# LoRa.net
KiCad netlist of a schematic drawn in Altium Designer
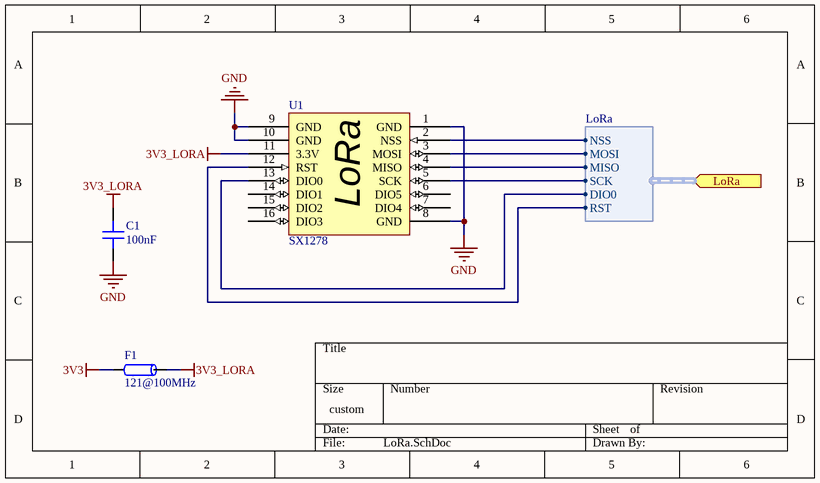
[diagram p0: LoRa.SchDoc]

(export (version "E")
  (design (tool "Eeschema 10.0.6"))
  (components
    (comp (ref "C1")
      (value "100nF")
      (footprint "CAP 0603_1608")
      (description "SMT Capacitor")
      (libsource (lib "Capacitor") (part "Cap 0603"))
    )
    (comp (ref "F1")
      (value "121@100MHz")
      (footprint "Ferrite-0805")
      (description "Ferrite Bead")
      (libsource (lib "Salman_lib") (part "Ferrite Bead"))
    )
    (comp (ref "U1")
      (value "SX1278")
      (footprint "LoRa-Ra-02")
      (libsource (lib "Salman_lib") (part "LoRa Ra-02"))
    )
  )
  (nets
    (net (code "2") (name "/DIO0") (class "Default")
      (node (ref "U1") (pin "13") (pinfunction "DIO0_13") (pintype "bidirectional"))
    )
    (net (code "3") (name "/MISO") (class "Default")
      (node (ref "U1") (pin "4") (pinfunction "MISO_4") (pintype "bidirectional"))
    )
    (net (code "4") (name "/MOSI") (class "Default")
      (node (ref "U1") (pin "3") (pinfunction "MOSI_3") (pintype "bidirectional"))
    )
    (net (code "5") (name "/NSS") (class "Default")
      (node (ref "U1") (pin "2") (pinfunction "NSS_2") (pintype "input"))
    )
    (net (code "6") (name "/RST") (class "Default")
      (node (ref "U1") (pin "12") (pinfunction "RST_12") (pintype "input"))
    )
    (net (code "7") (name "/SCK") (class "Default")
      (node (ref "U1") (pin "5") (pinfunction "SCK_5") (pintype "bidirectional"))
    )
    (net (code "9") (name "3V3") (class "Default")
      (node (ref "F1") (pin "1") (pinfunction "67_1") (pintype "passive"))
    )
    (net (code "10") (name "3V3_LORA") (class "Default")
      (node (ref "C1") (pin "2") (pinfunction "2_2") (pintype "passive"))
      (node (ref "F1") (pin "2") (pinfunction "66_2") (pintype "passive"))
      (node (ref "U1") (pin "11") (pinfunction "3.3V_11") (pintype "power_in"))
    )
    (net (code "11") (name "GND") (class "Default")
      (node (ref "C1") (pin "1") (pinfunction "1_1") (pintype "passive"))
      (node (ref "U1") (pin "1") (pinfunction "GND_1") (pintype "tri_state"))
      (node (ref "U1") (pin "10") (pinfunction "GND_10") (pintype "tri_state"))
      (node (ref "U1") (pin "8") (pinfunction "GND_8") (pintype "tri_state"))
      (node (ref "U1") (pin "9") (pinfunction "GND_9") (pintype "tri_state"))
    )
    (net (code "12") (name "unconnected-(U1-DIO1-Pad14)") (class "Default")
      (node (ref "U1") (pin "14") (pinfunction "DIO1_14") (pintype "bidirectional"))
    )
    (net (code "13") (name "unconnected-(U1-DIO2-Pad15)") (class "Default")
      (node (ref "U1") (pin "15") (pinfunction "DIO2_15") (pintype "bidirectional"))
    )
    (net (code "14") (name "unconnected-(U1-DIO3-Pad16)") (class "Default")
      (node (ref "U1") (pin "16") (pinfunction "DIO3_16") (pintype "bidirectional"))
    )
    (net (code "15") (name "unconnected-(U1-DIO4-Pad7)") (class "Default")
      (node (ref "U1") (pin "7") (pinfunction "DIO4_7") (pintype "bidirectional"))
    )
    (net (code "16") (name "unconnected-(U1-DIO5-Pad6)") (class "Default")
      (node (ref "U1") (pin "6") (pinfunction "DIO5_6") (pintype "bidirectional"))
    )
  )
)
